# Main.net
KiCad netlist of a schematic drawn in Altium Designer
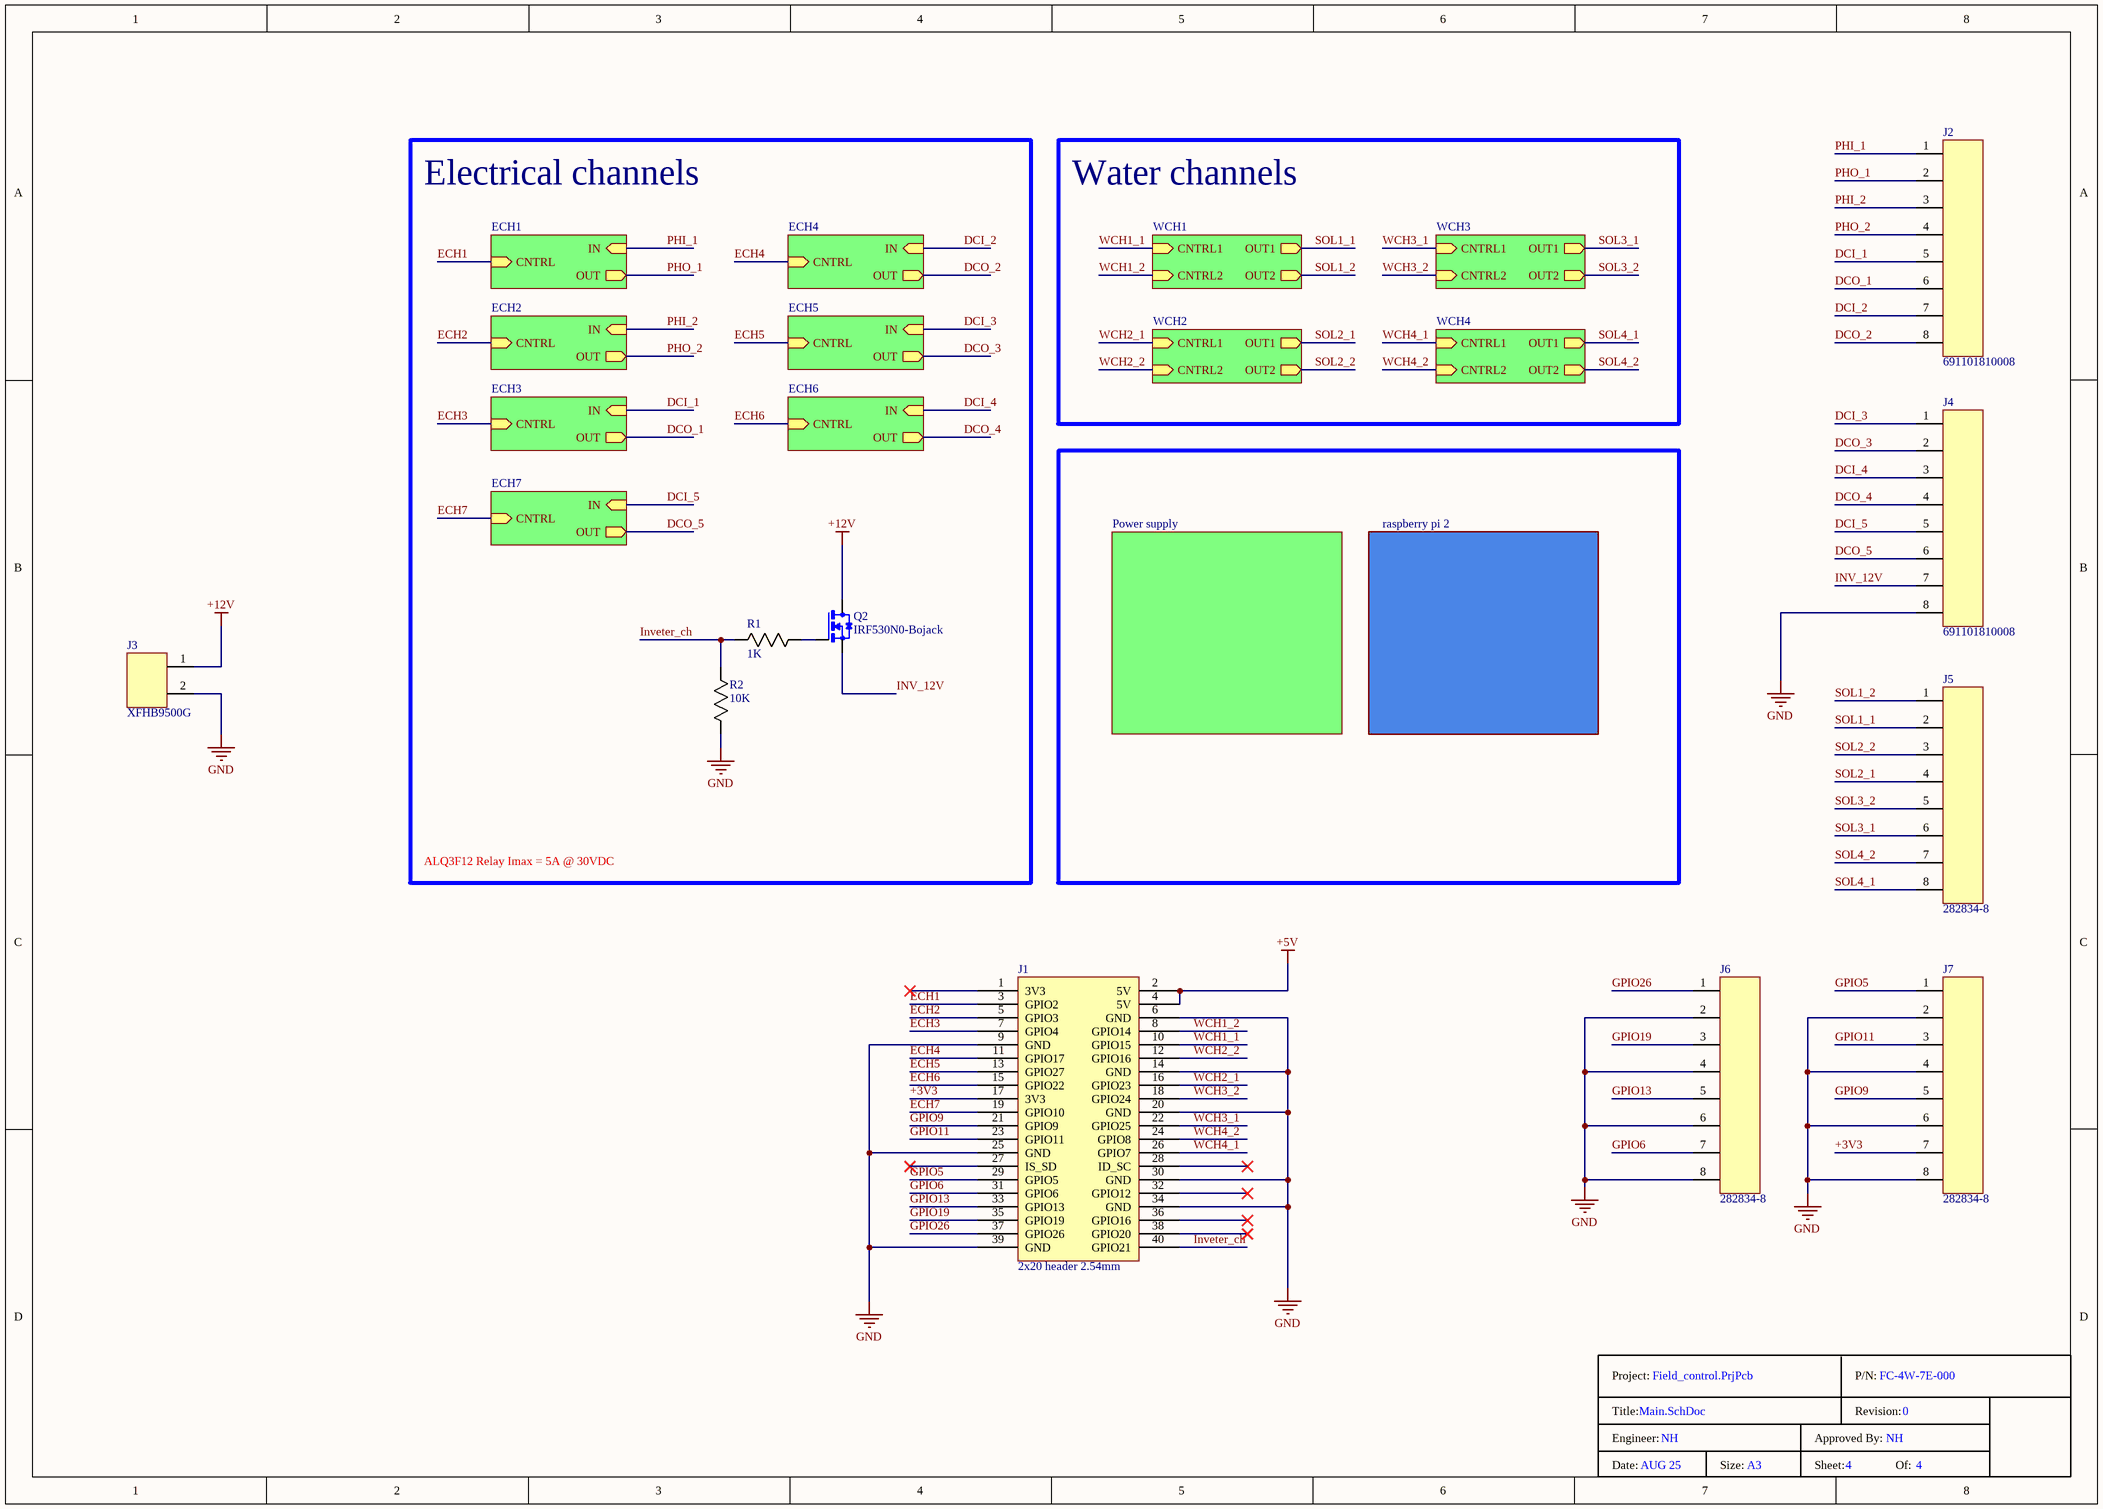
[diagram p0: Main.SchDoc]

(export (version "E")
  (design (tool "Eeschema 10.0.6"))
  (components
    (comp (ref "J1")
      (value "2x20 header 2.54mm")
      (footprint "2x20 2.54mm header")
      (libsource (lib "Connectors") (part "2x20 header 2.54mm"))
    )
    (comp (ref "J2")
      (value "691101810008")
      (footprint "691101810008")
      (description "8 Position Wire to Board Terminal Block Horizontal with Board 0.394\" (10.00mm) Through Hole")
      (fields (field (name "MANUFACTURER") "Würth Elektronik"))
      (libsource (lib "Connectors") (part "691101810008"))
    )
    (comp (ref "J3")
      (value "XFHB9500G")
      (footprint "XHFB9500G")
      (fields (field (name "MANUFACTURER") "XF"))
      (libsource (lib "Connectors") (part "XFHB9500G"))
    )
    (comp (ref "J4")
      (value "691101810008")
      (footprint "691101810008")
      (description "8 Position Wire to Board Terminal Block Horizontal with Board 0.394\" (10.00mm) Through Hole")
      (fields (field (name "MANUFACTURER") "Würth Elektronik"))
      (libsource (lib "Connectors") (part "691101810008"))
    )
    (comp (ref "J5")
      (value "282834-8")
      (footprint "282834-8")
      (description "TERM BLK 8P SIDE ENT 2.54MM PCB")
      (fields (field (name "MANUFACTURER") "TE Connectivity AMP Connectors"))
      (libsource (lib "Connectors") (part "282834-8"))
    )
    (comp (ref "J6")
      (value "282834-8")
      (footprint "282834-8")
      (description "TERM BLK 8P SIDE ENT 2.54MM PCB")
      (fields (field (name "MANUFACTURER") "TE Connectivity AMP Connectors"))
      (libsource (lib "Connectors") (part "282834-8"))
    )
    (comp (ref "J7")
      (value "282834-8")
      (footprint "282834-8")
      (description "TERM BLK 8P SIDE ENT 2.54MM PCB")
      (fields (field (name "MANUFACTURER") "TE Connectivity AMP Connectors"))
      (libsource (lib "Connectors") (part "282834-8"))
    )
    (comp (ref "Q2")
      (value "IRF530N0-Bojack")
      (footprint "SOT78(TO220AB)")
      (description "MOSFET N-CH 100V 17A TO220AB")
      (fields (field (name "MANUFACTURER") "Infineon Technologies"))
      (libsource (lib "Transistors") (part "IRF530N0-Bojack"))
    )
    (comp (ref "R1")
      (value "1K")
      (footprint "R0603")
      (fields (field (name "MANUFACTURER") "Stackpole Electronics Inc"))
      (libsource (lib "Resistors") (part "RMCF0603FT1K00"))
    )
    (comp (ref "R2")
      (value "10K")
      (footprint "R0603")
      (fields (field (name "MANUFACTURER") "Stackpole Electronics Inc"))
      (libsource (lib "Resistors") (part "RMCF0603FT10K0"))
    )
    (comp (ref "U3")
      (value "raspberry pi 2")
      (footprint "Raspberry pi 2")
      (libsource (lib "MISC") (part "raspberry pi 2"))
    )
  )
  (nets
    (net (code "1") (name "+5V") (class "Default")
      (node (ref "J1") (pin "2") (pinfunction "5V_2") (pintype "passive"))
      (node (ref "J1") (pin "4") (pinfunction "5V_4") (pintype "passive"))
    )
    (net (code "2") (name "+12V") (class "Default")
      (node (ref "J3") (pin "1") (pinfunction "1_1") (pintype "passive"))
      (node (ref "Q2") (pin "3") (pinfunction "D_3") (pintype "passive"))
    )
    (net (code "3") (name "/+3V3") (class "Default")
      (node (ref "J1") (pin "17") (pinfunction "3V3_17") (pintype "passive"))
      (node (ref "J7") (pin "7") (pinfunction "7_7") (pintype "passive"))
    )
    (net (code "4") (name "/DCI_1") (class "Default")
      (node (ref "J2") (pin "5") (pinfunction "5_5") (pintype "passive"))
    )
    (net (code "5") (name "/DCI_2") (class "Default")
      (node (ref "J2") (pin "7") (pinfunction "7_7") (pintype "passive"))
    )
    (net (code "6") (name "/DCI_3") (class "Default")
      (node (ref "J4") (pin "1") (pinfunction "1_1") (pintype "passive"))
    )
    (net (code "7") (name "/DCI_4") (class "Default")
      (node (ref "J4") (pin "3") (pinfunction "3_3") (pintype "passive"))
    )
    (net (code "8") (name "/DCI_5") (class "Default")
      (node (ref "J4") (pin "5") (pinfunction "5_5") (pintype "passive"))
    )
    (net (code "9") (name "/DCO_1") (class "Default")
      (node (ref "J2") (pin "6") (pinfunction "6_6") (pintype "passive"))
    )
    (net (code "10") (name "/DCO_2") (class "Default")
      (node (ref "J2") (pin "8") (pinfunction "8_8") (pintype "passive"))
    )
    (net (code "11") (name "/DCO_3") (class "Default")
      (node (ref "J4") (pin "2") (pinfunction "2_2") (pintype "passive"))
    )
    (net (code "12") (name "/DCO_4") (class "Default")
      (node (ref "J4") (pin "4") (pinfunction "4_4") (pintype "passive"))
    )
    (net (code "13") (name "/DCO_5") (class "Default")
      (node (ref "J4") (pin "6") (pinfunction "6_6") (pintype "passive"))
    )
    (net (code "14") (name "/ECH1") (class "Default")
      (node (ref "J1") (pin "3") (pinfunction "GPIO2_3") (pintype "passive"))
    )
    (net (code "15") (name "/ECH2") (class "Default")
      (node (ref "J1") (pin "5") (pinfunction "GPIO3_5") (pintype "passive"))
    )
    (net (code "16") (name "/ECH3") (class "Default")
      (node (ref "J1") (pin "7") (pinfunction "GPIO4_7") (pintype "passive"))
    )
    (net (code "17") (name "/ECH4") (class "Default")
      (node (ref "J1") (pin "11") (pinfunction "GPIO17_11") (pintype "passive"))
    )
    (net (code "18") (name "/ECH5") (class "Default")
      (node (ref "J1") (pin "13") (pinfunction "GPIO27_13") (pintype "passive"))
    )
    (net (code "19") (name "/ECH6") (class "Default")
      (node (ref "J1") (pin "15") (pinfunction "GPIO22_15") (pintype "passive"))
    )
    (net (code "20") (name "/ECH7") (class "Default")
      (node (ref "J1") (pin "19") (pinfunction "GPIO10_19") (pintype "passive"))
    )
    (net (code "21") (name "/GPIO5") (class "Default")
      (node (ref "J1") (pin "29") (pinfunction "GPIO5_29") (pintype "passive"))
      (node (ref "J7") (pin "1") (pinfunction "1_1") (pintype "passive"))
    )
    (net (code "22") (name "/GPIO6") (class "Default")
      (node (ref "J1") (pin "31") (pinfunction "GPIO6_31") (pintype "passive"))
      (node (ref "J6") (pin "7") (pinfunction "7_7") (pintype "passive"))
    )
    (net (code "23") (name "/GPIO9") (class "Default")
      (node (ref "J1") (pin "21") (pinfunction "GPIO9_21") (pintype "passive"))
      (node (ref "J7") (pin "5") (pinfunction "5_5") (pintype "passive"))
    )
    (net (code "24") (name "/GPIO11") (class "Default")
      (node (ref "J1") (pin "23") (pinfunction "GPIO11_23") (pintype "passive"))
      (node (ref "J7") (pin "3") (pinfunction "3_3") (pintype "passive"))
    )
    (net (code "25") (name "/GPIO13") (class "Default")
      (node (ref "J1") (pin "33") (pinfunction "GPIO13_33") (pintype "passive"))
      (node (ref "J6") (pin "5") (pinfunction "5_5") (pintype "passive"))
    )
    (net (code "26") (name "/GPIO19") (class "Default")
      (node (ref "J1") (pin "35") (pinfunction "GPIO19_35") (pintype "passive"))
      (node (ref "J6") (pin "3") (pinfunction "3_3") (pintype "passive"))
    )
    (net (code "27") (name "/GPIO26") (class "Default")
      (node (ref "J1") (pin "37") (pinfunction "GPIO26_37") (pintype "passive"))
      (node (ref "J6") (pin "1") (pinfunction "1_1") (pintype "passive"))
    )
    (net (code "28") (name "/INV_12V") (class "Default")
      (node (ref "J4") (pin "7") (pinfunction "7_7") (pintype "passive"))
      (node (ref "Q2") (pin "2") (pinfunction "S_2") (pintype "passive"))
    )
    (net (code "29") (name "/Inveter_ch") (class "Default")
      (node (ref "J1") (pin "40") (pinfunction "GPIO21_40") (pintype "passive"))
      (node (ref "R1") (pin "1") (pinfunction "1_1") (pintype "passive"))
      (node (ref "R2") (pin "2") (pinfunction "2_2") (pintype "passive"))
    )
    (net (code "30") (name "/PHI_1") (class "Default")
      (node (ref "J2") (pin "1") (pinfunction "1_1") (pintype "passive"))
    )
    (net (code "31") (name "/PHI_2") (class "Default")
      (node (ref "J2") (pin "3") (pinfunction "3_3") (pintype "passive"))
    )
    (net (code "32") (name "/PHO_1") (class "Default")
      (node (ref "J2") (pin "2") (pinfunction "2_2") (pintype "passive"))
    )
    (net (code "33") (name "/PHO_2") (class "Default")
      (node (ref "J2") (pin "4") (pinfunction "4_4") (pintype "passive"))
    )
    (net (code "34") (name "/SOL1_1") (class "Default")
      (node (ref "J5") (pin "2") (pinfunction "2_2") (pintype "passive"))
    )
    (net (code "35") (name "/SOL1_2") (class "Default")
      (node (ref "J5") (pin "1") (pinfunction "1_1") (pintype "passive"))
    )
    (net (code "36") (name "/SOL2_1") (class "Default")
      (node (ref "J5") (pin "4") (pinfunction "4_4") (pintype "passive"))
    )
    (net (code "37") (name "/SOL2_2") (class "Default")
      (node (ref "J5") (pin "3") (pinfunction "3_3") (pintype "passive"))
    )
    (net (code "38") (name "/SOL3_1") (class "Default")
      (node (ref "J5") (pin "6") (pinfunction "6_6") (pintype "passive"))
    )
    (net (code "39") (name "/SOL3_2") (class "Default")
      (node (ref "J5") (pin "5") (pinfunction "5_5") (pintype "passive"))
    )
    (net (code "40") (name "/SOL4_1") (class "Default")
      (node (ref "J5") (pin "8") (pinfunction "8_8") (pintype "passive"))
    )
    (net (code "41") (name "/SOL4_2") (class "Default")
      (node (ref "J5") (pin "7") (pinfunction "7_7") (pintype "passive"))
    )
    (net (code "42") (name "/WCH1_1") (class "Default")
      (node (ref "J1") (pin "10") (pinfunction "GPIO15_10") (pintype "passive"))
    )
    (net (code "43") (name "/WCH1_2") (class "Default")
      (node (ref "J1") (pin "8") (pinfunction "GPIO14_8") (pintype "passive"))
    )
    (net (code "44") (name "/WCH2_1") (class "Default")
      (node (ref "J1") (pin "16") (pinfunction "GPIO23_16") (pintype "passive"))
    )
    (net (code "45") (name "/WCH2_2") (class "Default")
      (node (ref "J1") (pin "12") (pinfunction "GPIO16_12") (pintype "passive"))
    )
    (net (code "46") (name "/WCH3_1") (class "Default")
      (node (ref "J1") (pin "22") (pinfunction "GPIO25_22") (pintype "passive"))
    )
    (net (code "47") (name "/WCH3_2") (class "Default")
      (node (ref "J1") (pin "18") (pinfunction "GPIO24_18") (pintype "passive"))
    )
    (net (code "48") (name "/WCH4_1") (class "Default")
      (node (ref "J1") (pin "26") (pinfunction "GPIO7_26") (pintype "passive"))
    )
    (net (code "49") (name "/WCH4_2") (class "Default")
      (node (ref "J1") (pin "24") (pinfunction "GPIO8_24") (pintype "passive"))
    )
    (net (code "50") (name "GND") (class "Default")
      (node (ref "J1") (pin "14") (pinfunction "GND_14") (pintype "passive"))
      (node (ref "J1") (pin "20") (pinfunction "GND_20") (pintype "passive"))
      (node (ref "J1") (pin "25") (pinfunction "GND_25") (pintype "passive"))
      (node (ref "J1") (pin "30") (pinfunction "GND_30") (pintype "passive"))
      (node (ref "J1") (pin "34") (pinfunction "GND_34") (pintype "passive"))
      (node (ref "J1") (pin "39") (pinfunction "GND_39") (pintype "passive"))
      (node (ref "J1") (pin "6") (pinfunction "GND_6") (pintype "passive"))
      (node (ref "J1") (pin "9") (pinfunction "GND_9") (pintype "passive"))
      (node (ref "J3") (pin "2") (pinfunction "2_2") (pintype "passive"))
      (node (ref "J4") (pin "8") (pinfunction "8_8") (pintype "passive"))
      (node (ref "J6") (pin "2") (pinfunction "2_2") (pintype "passive"))
      (node (ref "J6") (pin "4") (pinfunction "4_4") (pintype "passive"))
      (node (ref "J6") (pin "6") (pinfunction "6_6") (pintype "passive"))
      (node (ref "J6") (pin "8") (pinfunction "8_8") (pintype "passive"))
      (node (ref "J7") (pin "2") (pinfunction "2_2") (pintype "passive"))
      (node (ref "J7") (pin "4") (pinfunction "4_4") (pintype "passive"))
      (node (ref "J7") (pin "6") (pinfunction "6_6") (pintype "passive"))
      (node (ref "J7") (pin "8") (pinfunction "8_8") (pintype "passive"))
      (node (ref "R2") (pin "1") (pinfunction "1_1") (pintype "passive"))
    )
    (net (code "51") (name "Net-(Q2-G)") (class "Default")
      (node (ref "Q2") (pin "1") (pinfunction "G_1") (pintype "passive"))
      (node (ref "R1") (pin "2") (pinfunction "2_2") (pintype "passive"))
    )
    (net (code "52") (name "unconnected-(J1-3V3-Pad1)") (class "Default")
      (node (ref "J1") (pin "1") (pinfunction "3V3_1") (pintype "passive+no_connect"))
    )
    (net (code "53") (name "unconnected-(J1-GPIO12-Pad32)") (class "Default")
      (node (ref "J1") (pin "32") (pinfunction "GPIO12_32") (pintype "passive+no_connect"))
    )
    (net (code "54") (name "unconnected-(J1-GPIO16-Pad36)") (class "Default")
      (node (ref "J1") (pin "36") (pinfunction "GPIO16_36") (pintype "passive+no_connect"))
    )
    (net (code "55") (name "unconnected-(J1-GPIO20-Pad38)") (class "Default")
      (node (ref "J1") (pin "38") (pinfunction "GPIO20_38") (pintype "passive+no_connect"))
    )
    (net (code "56") (name "unconnected-(J1-ID_SC-Pad28)") (class "Default")
      (node (ref "J1") (pin "28") (pinfunction "ID_SC_28") (pintype "passive+no_connect"))
    )
    (net (code "57") (name "unconnected-(J1-IS_SD-Pad27)") (class "Default")
      (node (ref "J1") (pin "27") (pinfunction "IS_SD_27") (pintype "passive+no_connect"))
    )
  )
)
